# ATMega1284p.net
KiCad netlist of a schematic drawn in Altium Designer
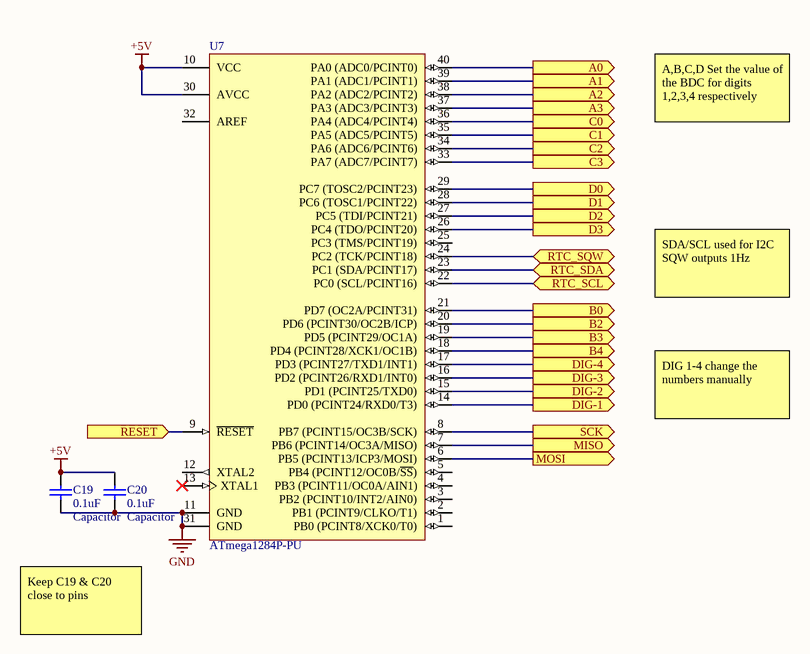
[diagram p0: ATMega1284p.SchDoc]

(export (version "E")
  (design (tool "Eeschema 10.0.6"))
  (components
    (comp (ref "C19")
      (value "0.1uF")
      (footprint "FOOTPRINT-1206-GEN")
      (description "CAP CER 0.1UF 50V X7R 1206")
      (fields
        (field (name "PART NUMBER") "1276-7034-1-ND")
        (field (name "TYPE") "Capacitor")
        (field (name "Comment") "Capacitor - 0.1uF - 1206")
        (field (name "PUBLISHER") "Altium Limited")
      )
      (libsource (lib "University of California Riverside - FSAE") (part "Symbol"))
    )
    (comp (ref "C20")
      (value "0.1uF")
      (footprint "FOOTPRINT-1206-GEN")
      (description "CAP CER 0.1UF 50V X7R 1206")
      (fields
        (field (name "PART NUMBER") "1276-7034-1-ND")
        (field (name "TYPE") "Capacitor")
        (field (name "Comment") "Capacitor - 0.1uF - 1206")
        (field (name "PUBLISHER") "Altium Limited")
      )
      (libsource (lib "University of California Riverside - FSAE") (part "Symbol"))
    )
    (comp (ref "U7")
      (value "ATmega1284P-PU")
      (footprint "40P6")
      (libsource (lib "Altium Content Vault") (part "MC-8B-ATM128-IL40"))
    )
  )
  (nets
    (net (code "1") (name "+5V") (class "Default")
      (node (ref "C19") (pin "2") (pinfunction "2_2") (pintype "passive"))
      (node (ref "C20") (pin "2") (pinfunction "2_2") (pintype "passive"))
      (node (ref "U7") (pin "10") (pinfunction "VCC_10") (pintype "power_in"))
      (node (ref "U7") (pin "30") (pinfunction "AVCC_30") (pintype "power_in"))
    )
    (net (code "2") (name "/A0") (class "Default")
      (node (ref "U7") (pin "40") (pinfunction "PA0_(ADC0/PCINT0)_40") (pintype "bidirectional"))
    )
    (net (code "3") (name "/A1") (class "Default")
      (node (ref "U7") (pin "39") (pinfunction "PA1_(ADC1/PCINT1)_39") (pintype "bidirectional"))
    )
    (net (code "4") (name "/A2") (class "Default")
      (node (ref "U7") (pin "38") (pinfunction "PA2_(ADC2/PCINT2)_38") (pintype "bidirectional"))
    )
    (net (code "5") (name "/A3") (class "Default")
      (node (ref "U7") (pin "37") (pinfunction "PA3_(ADC3/PCINT3)_37") (pintype "bidirectional"))
    )
    (net (code "6") (name "/B0") (class "Default")
      (node (ref "U7") (pin "21") (pinfunction "PD7_(OC2A/PCINT31)_21") (pintype "bidirectional"))
    )
    (net (code "7") (name "/B2") (class "Default")
      (node (ref "U7") (pin "20") (pinfunction "PD6_(PCINT30/OC2B/ICP)_20") (pintype "bidirectional"))
    )
    (net (code "8") (name "/B3") (class "Default")
      (node (ref "U7") (pin "19") (pinfunction "PD5_(PCINT29/OC1A)_19") (pintype "bidirectional"))
    )
    (net (code "9") (name "/B4") (class "Default")
      (node (ref "U7") (pin "18") (pinfunction "PD4_(PCINT28/XCK1/OC1B)_18") (pintype "bidirectional"))
    )
    (net (code "10") (name "/C0") (class "Default")
      (node (ref "U7") (pin "36") (pinfunction "PA4_(ADC4/PCINT4)_36") (pintype "bidirectional"))
    )
    (net (code "11") (name "/C1") (class "Default")
      (node (ref "U7") (pin "35") (pinfunction "PA5_(ADC5/PCINT5)_35") (pintype "bidirectional"))
    )
    (net (code "12") (name "/C2") (class "Default")
      (node (ref "U7") (pin "34") (pinfunction "PA6_(ADC6/PCINT6)_34") (pintype "bidirectional"))
    )
    (net (code "13") (name "/C3") (class "Default")
      (node (ref "U7") (pin "33") (pinfunction "PA7_(ADC7/PCINT7)_33") (pintype "bidirectional"))
    )
    (net (code "14") (name "/D0") (class "Default")
      (node (ref "U7") (pin "29") (pinfunction "PC7_(TOSC2/PCINT23)_29") (pintype "bidirectional"))
    )
    (net (code "15") (name "/D1") (class "Default")
      (node (ref "U7") (pin "28") (pinfunction "PC6_(TOSC1/PCINT22)_28") (pintype "bidirectional"))
    )
    (net (code "16") (name "/D2") (class "Default")
      (node (ref "U7") (pin "27") (pinfunction "PC5_(TDI/PCINT21)_27") (pintype "bidirectional"))
    )
    (net (code "17") (name "/D3") (class "Default")
      (node (ref "U7") (pin "26") (pinfunction "PC4_(TDO/PCINT20)_26") (pintype "bidirectional"))
    )
    (net (code "18") (name "/DIG-1") (class "Default")
      (node (ref "U7") (pin "14") (pinfunction "PD0_(PCINT24/RXD0/T3)_14") (pintype "bidirectional"))
    )
    (net (code "19") (name "/DIG-2") (class "Default")
      (node (ref "U7") (pin "15") (pinfunction "PD1_(PCINT25/TXD0)_15") (pintype "bidirectional"))
    )
    (net (code "20") (name "/DIG-3") (class "Default")
      (node (ref "U7") (pin "16") (pinfunction "PD2_(PCINT26/RXD1/INT0)_16") (pintype "bidirectional"))
    )
    (net (code "21") (name "/DIG-4") (class "Default")
      (node (ref "U7") (pin "17") (pinfunction "PD3_(PCINT27/TXD1/INT1)_17") (pintype "bidirectional"))
    )
    (net (code "22") (name "/MISO") (class "Default")
      (node (ref "U7") (pin "7") (pinfunction "PB6_(PCINT14/OC3A/MISO)_7") (pintype "bidirectional"))
    )
    (net (code "23") (name "/MOSI") (class "Default")
      (node (ref "U7") (pin "6") (pinfunction "PB5_(PCINT13/ICP3/MOSI)_6") (pintype "bidirectional"))
    )
    (net (code "24") (name "/RESET") (class "Default")
      (node (ref "U7") (pin "9") (pinfunction "~{RESET}_9") (pintype "input"))
    )
    (net (code "25") (name "/RTC_SCL") (class "Default")
      (node (ref "U7") (pin "22") (pinfunction "PC0_(SCL/PCINT16)_22") (pintype "bidirectional"))
    )
    (net (code "26") (name "/RTC_SDA") (class "Default")
      (node (ref "U7") (pin "23") (pinfunction "PC1_(SDA/PCINT17)_23") (pintype "bidirectional"))
    )
    (net (code "27") (name "/RTC_SQW") (class "Default")
      (node (ref "U7") (pin "24") (pinfunction "PC2_(TCK/PCINT18)_24") (pintype "bidirectional"))
    )
    (net (code "28") (name "/SCK") (class "Default")
      (node (ref "U7") (pin "8") (pinfunction "PB7_(PCINT15/OC3B/SCK)_8") (pintype "bidirectional"))
    )
    (net (code "29") (name "GND") (class "Default")
      (node (ref "C19") (pin "1") (pinfunction "1_1") (pintype "passive"))
      (node (ref "C20") (pin "1") (pinfunction "1_1") (pintype "passive"))
      (node (ref "U7") (pin "11") (pinfunction "GND_11") (pintype "power_in"))
      (node (ref "U7") (pin "31") (pinfunction "GND_31") (pintype "power_in"))
    )
    (net (code "30") (name "unconnected-(U7-AREF-Pad32)") (class "Default")
      (node (ref "U7") (pin "32") (pinfunction "AREF_32") (pintype "power_in"))
    )
    (net (code "31") (name "unconnected-(U7-PB0_(PCINT8{slash}XCK0{slash}T0)-Pad1)") (class "Default")
      (node (ref "U7") (pin "1") (pinfunction "PB0_(PCINT8/XCK0/T0)_1") (pintype "bidirectional"))
    )
    (net (code "32") (name "unconnected-(U7-PB1_(PCINT9{slash}CLKO{slash}T1)-Pad2)") (class "Default")
      (node (ref "U7") (pin "2") (pinfunction "PB1_(PCINT9/CLKO/T1)_2") (pintype "bidirectional"))
    )
    (net (code "33") (name "unconnected-(U7-PB2_(PCINT10{slash}INT2{slash}AIN0)-Pad3)") (class "Default")
      (node (ref "U7") (pin "3") (pinfunction "PB2_(PCINT10/INT2/AIN0)_3") (pintype "bidirectional"))
    )
    (net (code "34") (name "unconnected-(U7-PB3_(PCINT11{slash}OC0A{slash}AIN1)-Pad4)") (class "Default")
      (node (ref "U7") (pin "4") (pinfunction "PB3_(PCINT11/OC0A/AIN1)_4") (pintype "bidirectional"))
    )
    (net (code "35") (name "unconnected-(U7-PB4_(PCINT12{slash}OC0B{slash}~{SS})-Pad5)") (class "Default")
      (node (ref "U7") (pin "5") (pinfunction "PB4_(PCINT12/OC0B/~{SS})_5") (pintype "bidirectional"))
    )
    (net (code "36") (name "unconnected-(U7-PC3_(TMS{slash}PCINT19)-Pad25)") (class "Default")
      (node (ref "U7") (pin "25") (pinfunction "PC3_(TMS/PCINT19)_25") (pintype "bidirectional"))
    )
    (net (code "37") (name "unconnected-(U7-XTAL1-Pad13)") (class "Default")
      (node (ref "U7") (pin "13") (pinfunction "XTAL1_13") (pintype "input+no_connect"))
    )
    (net (code "38") (name "unconnected-(U7-XTAL2-Pad12)") (class "Default")
      (node (ref "U7") (pin "12") (pinfunction "XTAL2_12") (pintype "output"))
    )
  )
)
